# MV500-BASIC-BOTTOM.net
KiCad netlist of a schematic drawn in EAGLE
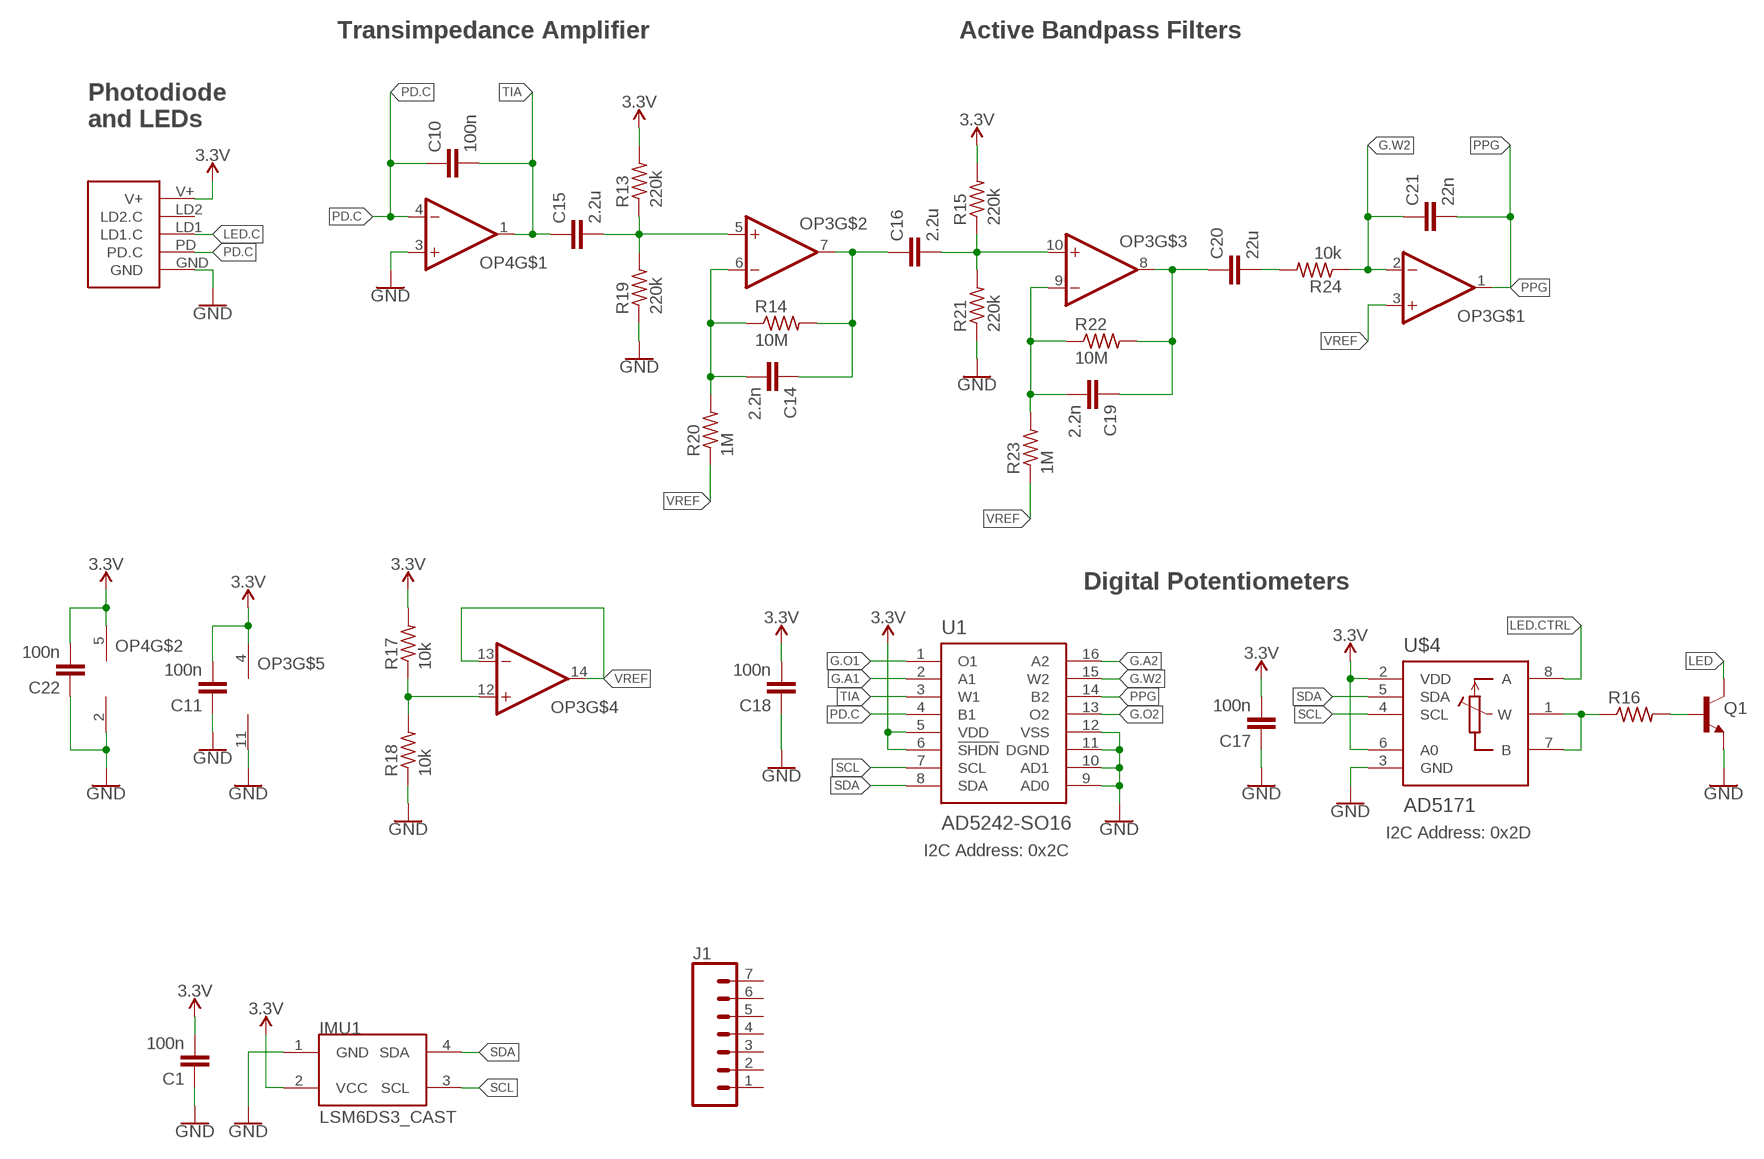
[diagram p0: schematic, sheet 1]

(export (version "E")
  (design (tool "Eeschema 10.0.6"))
  (components
    (comp (ref "C1")
      (value "100n")
      (footprint "eagle-import:C0603")
      (libsource (lib "eagle-import") (part "CAPACITOR0603"))
    )
    (comp (ref "C10")
      (value "100n")
      (footprint "eagle-import:C0603")
      (libsource (lib "eagle-import") (part "CAPACITOR0603"))
    )
    (comp (ref "C11")
      (value "100n")
      (footprint "eagle-import:C0603")
      (libsource (lib "eagle-import") (part "CAPACITOR0603"))
    )
    (comp (ref "C14")
      (value "2.2n")
      (footprint "eagle-import:C0603")
      (libsource (lib "eagle-import") (part "CAPACITOR0603"))
    )
    (comp (ref "C15")
      (value "2.2u")
      (footprint "eagle-import:C0603")
      (libsource (lib "eagle-import") (part "CAPACITOR0603"))
    )
    (comp (ref "C16")
      (value "2.2u")
      (footprint "eagle-import:C0603")
      (libsource (lib "eagle-import") (part "CAPACITOR0603"))
    )
    (comp (ref "C17")
      (value "100n")
      (footprint "eagle-import:C0603")
      (libsource (lib "eagle-import") (part "CAPACITOR0603"))
    )
    (comp (ref "C18")
      (value "100n")
      (footprint "eagle-import:C0603")
      (libsource (lib "eagle-import") (part "CAPACITOR0603"))
    )
    (comp (ref "C19")
      (value "2.2n")
      (footprint "eagle-import:C0603")
      (libsource (lib "eagle-import") (part "CAPACITOR0603"))
    )
    (comp (ref "C20")
      (value "22u")
      (footprint "eagle-import:C0603")
      (libsource (lib "eagle-import") (part "CAPACITOR0603"))
    )
    (comp (ref "C21")
      (value "22n")
      (footprint "eagle-import:C0603")
      (libsource (lib "eagle-import") (part "CAPACITOR0603"))
    )
    (comp (ref "C22")
      (value "100n")
      (footprint "eagle-import:C0603")
      (libsource (lib "eagle-import") (part "CAPACITOR0603"))
    )
    (comp (ref "IMU1")
      (value "LSM6DS3_CAST")
      (footprint "eagle-import:LSM6DS3_CAST")
      (libsource (lib "eagle-import") (part "LSM6DS3_CAST"))
    )
    (comp (ref "J1")
      (value "CONN_07")
      (footprint "eagle-import:1X07")
      (libsource (lib "eagle-import") (part "CONN_07"))
    )
    (comp (ref "OP3")
      (value "OP-QUAD-SO14")
      (footprint "eagle-import:SO14")
      (libsource (lib "eagle-import") (part "OP-QUAD-SO14"))
    )
    (comp (ref "OP4")
      (value "OP-SINGLEOT")
      (footprint "eagle-import:SOT23-5")
      (libsource (lib "eagle-import") (part "OP-SINGLEOT"))
    )
    (comp (ref "Q1")
      (value "NPN-GENERIC")
      (footprint "eagle-import:SOT23-3")
      (libsource (lib "eagle-import") (part "NPN-GENERIC"))
    )
    (comp (ref "R13")
      (value "220k")
      (footprint "eagle-import:R0603")
      (libsource (lib "eagle-import") (part "RESISTOR0603"))
    )
    (comp (ref "R14")
      (value "10M")
      (footprint "eagle-import:R0603")
      (libsource (lib "eagle-import") (part "RESISTOR0603"))
    )
    (comp (ref "R15")
      (value "220k")
      (footprint "eagle-import:R0603")
      (libsource (lib "eagle-import") (part "RESISTOR0603"))
    )
    (comp (ref "R16")
      (value "RESISTOR0603")
      (footprint "eagle-import:R0603")
      (libsource (lib "eagle-import") (part "RESISTOR0603"))
    )
    (comp (ref "R17")
      (value "10k")
      (footprint "eagle-import:R0402")
      (libsource (lib "eagle-import") (part "RESISTOR0402"))
    )
    (comp (ref "R18")
      (value "10k")
      (footprint "eagle-import:R0402")
      (libsource (lib "eagle-import") (part "RESISTOR0402"))
    )
    (comp (ref "R19")
      (value "220k")
      (footprint "eagle-import:R0603")
      (libsource (lib "eagle-import") (part "RESISTOR0603"))
    )
    (comp (ref "R20")
      (value "1M")
      (footprint "eagle-import:R0603")
      (libsource (lib "eagle-import") (part "RESISTOR0603"))
    )
    (comp (ref "R21")
      (value "220k")
      (footprint "eagle-import:R0603")
      (libsource (lib "eagle-import") (part "RESISTOR0603"))
    )
    (comp (ref "R22")
      (value "10M")
      (footprint "eagle-import:R0603")
      (libsource (lib "eagle-import") (part "RESISTOR0603"))
    )
    (comp (ref "R23")
      (value "1M")
      (footprint "eagle-import:R0603")
      (libsource (lib "eagle-import") (part "RESISTOR0603"))
    )
    (comp (ref "R24")
      (value "10k")
      (footprint "eagle-import:R0603")
      (libsource (lib "eagle-import") (part "RESISTOR0603"))
    )
    (comp (ref "U$3")
      (value "PPG.MODULE.2")
      (footprint "eagle-import:PPG.MODULE.2")
      (libsource (lib "eagle-import") (part "PPG.MODULE.2"))
    )
    (comp (ref "U$4")
      (value "AD5171")
      (footprint "eagle-import:SOT-23-8")
      (libsource (lib "eagle-import") (part "AD5171"))
    )
    (comp (ref "U1")
      (value "AD5242-SO16")
      (footprint "eagle-import:SO16")
      (libsource (lib "eagle-import") (part "AD5242-SO16"))
    )
  )
  (nets
    (net (code "1") (name "3.3V") (class "Default")
      (node (ref "C1") (pin "2") (pinfunction "2_2") (pintype "passive"))
      (node (ref "C11") (pin "2") (pinfunction "2_2") (pintype "passive"))
      (node (ref "C17") (pin "2") (pinfunction "2_2") (pintype "passive"))
      (node (ref "C18") (pin "2") (pinfunction "2_2") (pintype "passive"))
      (node (ref "C22") (pin "2") (pinfunction "2_2") (pintype "passive"))
      (node (ref "IMU1") (pin "2") (pinfunction "VCC_2") (pintype "bidirectional"))
      (node (ref "OP3") (pin "4") (pinfunction "V+_4") (pintype "power_in"))
      (node (ref "OP4") (pin "5") (pinfunction "V+_5") (pintype "power_in"))
      (node (ref "R13") (pin "2") (pinfunction "2_2") (pintype "passive"))
      (node (ref "R15") (pin "2") (pinfunction "2_2") (pintype "passive"))
      (node (ref "R17") (pin "2") (pinfunction "2_2") (pintype "passive"))
      (node (ref "U$3") (pin "V+") (pinfunction "V+_V+") (pintype "bidirectional"))
      (node (ref "U$4") (pin "2") (pinfunction "VDD_2") (pintype "bidirectional"))
      (node (ref "U$4") (pin "6") (pinfunction "A0_6") (pintype "bidirectional"))
      (node (ref "U1") (pin "5") (pinfunction "VDD_5") (pintype "bidirectional"))
      (node (ref "U1") (pin "6") (pinfunction "~{SHDN}_6") (pintype "bidirectional"))
    )
    (net (code "2") (name "G.A1") (class "Default")
      (node (ref "U1") (pin "2") (pinfunction "A1_2") (pintype "bidirectional"))
    )
    (net (code "3") (name "G.A2") (class "Default")
      (node (ref "U1") (pin "16") (pinfunction "A2_16") (pintype "bidirectional"))
    )
    (net (code "4") (name "G.O1") (class "Default")
      (node (ref "U1") (pin "1") (pinfunction "O1_1") (pintype "bidirectional"))
    )
    (net (code "5") (name "G.O2") (class "Default")
      (node (ref "U1") (pin "13") (pinfunction "O2_13") (pintype "bidirectional"))
    )
    (net (code "6") (name "G.W2") (class "Default")
      (node (ref "C21") (pin "1") (pinfunction "1_1") (pintype "passive"))
      (node (ref "OP3") (pin "2") (pinfunction "-IN_2") (pintype "input"))
      (node (ref "R24") (pin "1") (pinfunction "1_1") (pintype "passive"))
      (node (ref "U1") (pin "15") (pinfunction "W2_15") (pintype "bidirectional"))
    )
    (net (code "7") (name "GND") (class "Default")
      (node (ref "C1") (pin "1") (pinfunction "1_1") (pintype "passive"))
      (node (ref "C11") (pin "1") (pinfunction "1_1") (pintype "passive"))
      (node (ref "C17") (pin "1") (pinfunction "1_1") (pintype "passive"))
      (node (ref "C18") (pin "1") (pinfunction "1_1") (pintype "passive"))
      (node (ref "C22") (pin "1") (pinfunction "1_1") (pintype "passive"))
      (node (ref "IMU1") (pin "1") (pinfunction "GND_1") (pintype "bidirectional"))
      (node (ref "OP3") (pin "11") (pinfunction "V-_11") (pintype "power_in"))
      (node (ref "OP4") (pin "2") (pinfunction "V-_2") (pintype "power_in"))
      (node (ref "OP4") (pin "3") (pinfunction "+IN_3") (pintype "input"))
      (node (ref "Q1") (pin "2") (pinfunction "E_2") (pintype "passive"))
      (node (ref "R18") (pin "1") (pinfunction "1_1") (pintype "passive"))
      (node (ref "R19") (pin "1") (pinfunction "1_1") (pintype "passive"))
      (node (ref "R21") (pin "1") (pinfunction "1_1") (pintype "passive"))
      (node (ref "U$3") (pin "GND") (pinfunction "GND_GND") (pintype "bidirectional"))
      (node (ref "U$4") (pin "3") (pinfunction "GND_3") (pintype "bidirectional"))
      (node (ref "U1") (pin "10") (pinfunction "AD1_10") (pintype "bidirectional"))
      (node (ref "U1") (pin "11") (pinfunction "DGND_11") (pintype "bidirectional"))
      (node (ref "U1") (pin "12") (pinfunction "VSS_12") (pintype "bidirectional"))
      (node (ref "U1") (pin "9") (pinfunction "AD0_9") (pintype "bidirectional"))
    )
    (net (code "8") (name "LED") (class "Default")
      (node (ref "Q1") (pin "3") (pinfunction "C_3") (pintype "passive"))
    )
    (net (code "9") (name "LED.C") (class "Default")
      (node (ref "U$3") (pin "LD1") (pinfunction "LD1.C_LD1") (pintype "bidirectional"))
    )
    (net (code "10") (name "LED.CTRL") (class "Default")
      (node (ref "U$4") (pin "8") (pinfunction "A_8") (pintype "bidirectional"))
    )
    (net (code "11") (name "Net-(C20-Pad2)") (class "Default")
      (node (ref "C20") (pin "2") (pinfunction "2_2") (pintype "passive"))
      (node (ref "R24") (pin "2") (pinfunction "2_2") (pintype "passive"))
    )
    (net (code "12") (name "Net-(OP3B-+IN)") (class "Default")
      (node (ref "C15") (pin "2") (pinfunction "2_2") (pintype "passive"))
      (node (ref "OP3") (pin "5") (pinfunction "+IN_5") (pintype "input"))
      (node (ref "R13") (pin "1") (pinfunction "1_1") (pintype "passive"))
      (node (ref "R19") (pin "2") (pinfunction "2_2") (pintype "passive"))
    )
    (net (code "13") (name "Net-(OP3B--IN)") (class "Default")
      (node (ref "C14") (pin "2") (pinfunction "2_2") (pintype "passive"))
      (node (ref "OP3") (pin "6") (pinfunction "-IN_6") (pintype "input"))
      (node (ref "R14") (pin "1") (pinfunction "1_1") (pintype "passive"))
      (node (ref "R20") (pin "2") (pinfunction "2_2") (pintype "passive"))
    )
    (net (code "14") (name "Net-(OP3B-OUT)") (class "Default")
      (node (ref "C14") (pin "1") (pinfunction "1_1") (pintype "passive"))
      (node (ref "C16") (pin "1") (pinfunction "1_1") (pintype "passive"))
      (node (ref "OP3") (pin "7") (pinfunction "OUT_7") (pintype "output"))
      (node (ref "R14") (pin "2") (pinfunction "2_2") (pintype "passive"))
    )
    (net (code "15") (name "Net-(OP3C-+IN)") (class "Default")
      (node (ref "C16") (pin "2") (pinfunction "2_2") (pintype "passive"))
      (node (ref "OP3") (pin "10") (pinfunction "+IN_10") (pintype "input"))
      (node (ref "R15") (pin "1") (pinfunction "1_1") (pintype "passive"))
      (node (ref "R21") (pin "2") (pinfunction "2_2") (pintype "passive"))
    )
    (net (code "16") (name "Net-(OP3C--IN)") (class "Default")
      (node (ref "C19") (pin "2") (pinfunction "2_2") (pintype "passive"))
      (node (ref "OP3") (pin "9") (pinfunction "-IN_9") (pintype "input"))
      (node (ref "R22") (pin "1") (pinfunction "1_1") (pintype "passive"))
      (node (ref "R23") (pin "2") (pinfunction "2_2") (pintype "passive"))
    )
    (net (code "17") (name "Net-(OP3C-OUT)") (class "Default")
      (node (ref "C19") (pin "1") (pinfunction "1_1") (pintype "passive"))
      (node (ref "C20") (pin "1") (pinfunction "1_1") (pintype "passive"))
      (node (ref "OP3") (pin "8") (pinfunction "OUT_8") (pintype "output"))
      (node (ref "R22") (pin "2") (pinfunction "2_2") (pintype "passive"))
    )
    (net (code "18") (name "Net-(OP3D-+IN)") (class "Default")
      (node (ref "OP3") (pin "12") (pinfunction "+IN_12") (pintype "input"))
      (node (ref "R17") (pin "1") (pinfunction "1_1") (pintype "passive"))
      (node (ref "R18") (pin "2") (pinfunction "2_2") (pintype "passive"))
    )
    (net (code "19") (name "Net-(Q1-B)") (class "Default")
      (node (ref "Q1") (pin "1") (pinfunction "B_1") (pintype "passive"))
      (node (ref "R16") (pin "2") (pinfunction "2_2") (pintype "passive"))
    )
    (net (code "20") (name "Net-(U$4-B)") (class "Default")
      (node (ref "R16") (pin "1") (pinfunction "1_1") (pintype "passive"))
      (node (ref "U$4") (pin "1") (pinfunction "W_1") (pintype "bidirectional"))
      (node (ref "U$4") (pin "7") (pinfunction "B_7") (pintype "bidirectional"))
    )
    (net (code "21") (name "PD.C") (class "Default")
      (node (ref "C10") (pin "1") (pinfunction "1_1") (pintype "passive"))
      (node (ref "OP4") (pin "4") (pinfunction "-IN_4") (pintype "input"))
      (node (ref "U$3") (pin "PD") (pinfunction "PD.C_PD") (pintype "bidirectional"))
      (node (ref "U1") (pin "4") (pinfunction "B1_4") (pintype "bidirectional"))
    )
    (net (code "22") (name "PPG") (class "Default")
      (node (ref "C21") (pin "2") (pinfunction "2_2") (pintype "passive"))
      (node (ref "OP3") (pin "1") (pinfunction "OUT_1") (pintype "output"))
      (node (ref "U1") (pin "14") (pinfunction "B2_14") (pintype "bidirectional"))
    )
    (net (code "23") (name "SCL") (class "Default")
      (node (ref "IMU1") (pin "3") (pinfunction "SCL_3") (pintype "bidirectional"))
      (node (ref "U$4") (pin "4") (pinfunction "SCL_4") (pintype "bidirectional"))
      (node (ref "U1") (pin "7") (pinfunction "SCL_7") (pintype "bidirectional"))
    )
    (net (code "24") (name "SDA") (class "Default")
      (node (ref "IMU1") (pin "4") (pinfunction "SDA_4") (pintype "bidirectional"))
      (node (ref "U$4") (pin "5") (pinfunction "SDA_5") (pintype "bidirectional"))
      (node (ref "U1") (pin "8") (pinfunction "SDA_8") (pintype "bidirectional"))
    )
    (net (code "25") (name "TIA") (class "Default")
      (node (ref "C10") (pin "2") (pinfunction "2_2") (pintype "passive"))
      (node (ref "C15") (pin "1") (pinfunction "1_1") (pintype "passive"))
      (node (ref "OP4") (pin "1") (pinfunction "OUT_1") (pintype "output"))
      (node (ref "U1") (pin "3") (pinfunction "W1_3") (pintype "bidirectional"))
    )
    (net (code "26") (name "VREF") (class "Default")
      (node (ref "OP3") (pin "13") (pinfunction "-IN_13") (pintype "input"))
      (node (ref "OP3") (pin "14") (pinfunction "OUT_14") (pintype "output"))
      (node (ref "OP3") (pin "3") (pinfunction "+IN_3") (pintype "input"))
      (node (ref "R20") (pin "1") (pinfunction "1_1") (pintype "passive"))
      (node (ref "R23") (pin "1") (pinfunction "1_1") (pintype "passive"))
    )
    (net (code "27") (name "unconnected-(J1-Pad1)") (class "Default")
      (node (ref "J1") (pin "1") (pinfunction "1_1") (pintype "passive"))
    )
    (net (code "28") (name "unconnected-(J1-Pad2)") (class "Default")
      (node (ref "J1") (pin "2") (pinfunction "2_2") (pintype "passive"))
    )
    (net (code "29") (name "unconnected-(J1-Pad3)") (class "Default")
      (node (ref "J1") (pin "3") (pinfunction "3_3") (pintype "passive"))
    )
    (net (code "30") (name "unconnected-(J1-Pad4)") (class "Default")
      (node (ref "J1") (pin "4") (pinfunction "4_4") (pintype "passive"))
    )
    (net (code "31") (name "unconnected-(J1-Pad5)") (class "Default")
      (node (ref "J1") (pin "5") (pinfunction "5_5") (pintype "passive"))
    )
    (net (code "32") (name "unconnected-(J1-Pad6)") (class "Default")
      (node (ref "J1") (pin "6") (pinfunction "6_6") (pintype "passive"))
    )
    (net (code "33") (name "unconnected-(J1-Pad7)") (class "Default")
      (node (ref "J1") (pin "7") (pinfunction "7_7") (pintype "passive"))
    )
    (net (code "34") (name "unconnected-(U$3-LD2.C-PadLD2)") (class "Default")
      (node (ref "U$3") (pin "LD2") (pinfunction "LD2.C_LD2") (pintype "bidirectional"))
    )
  )
)
